# Demux.net
KiCad netlist of a schematic drawn in Altium Designer
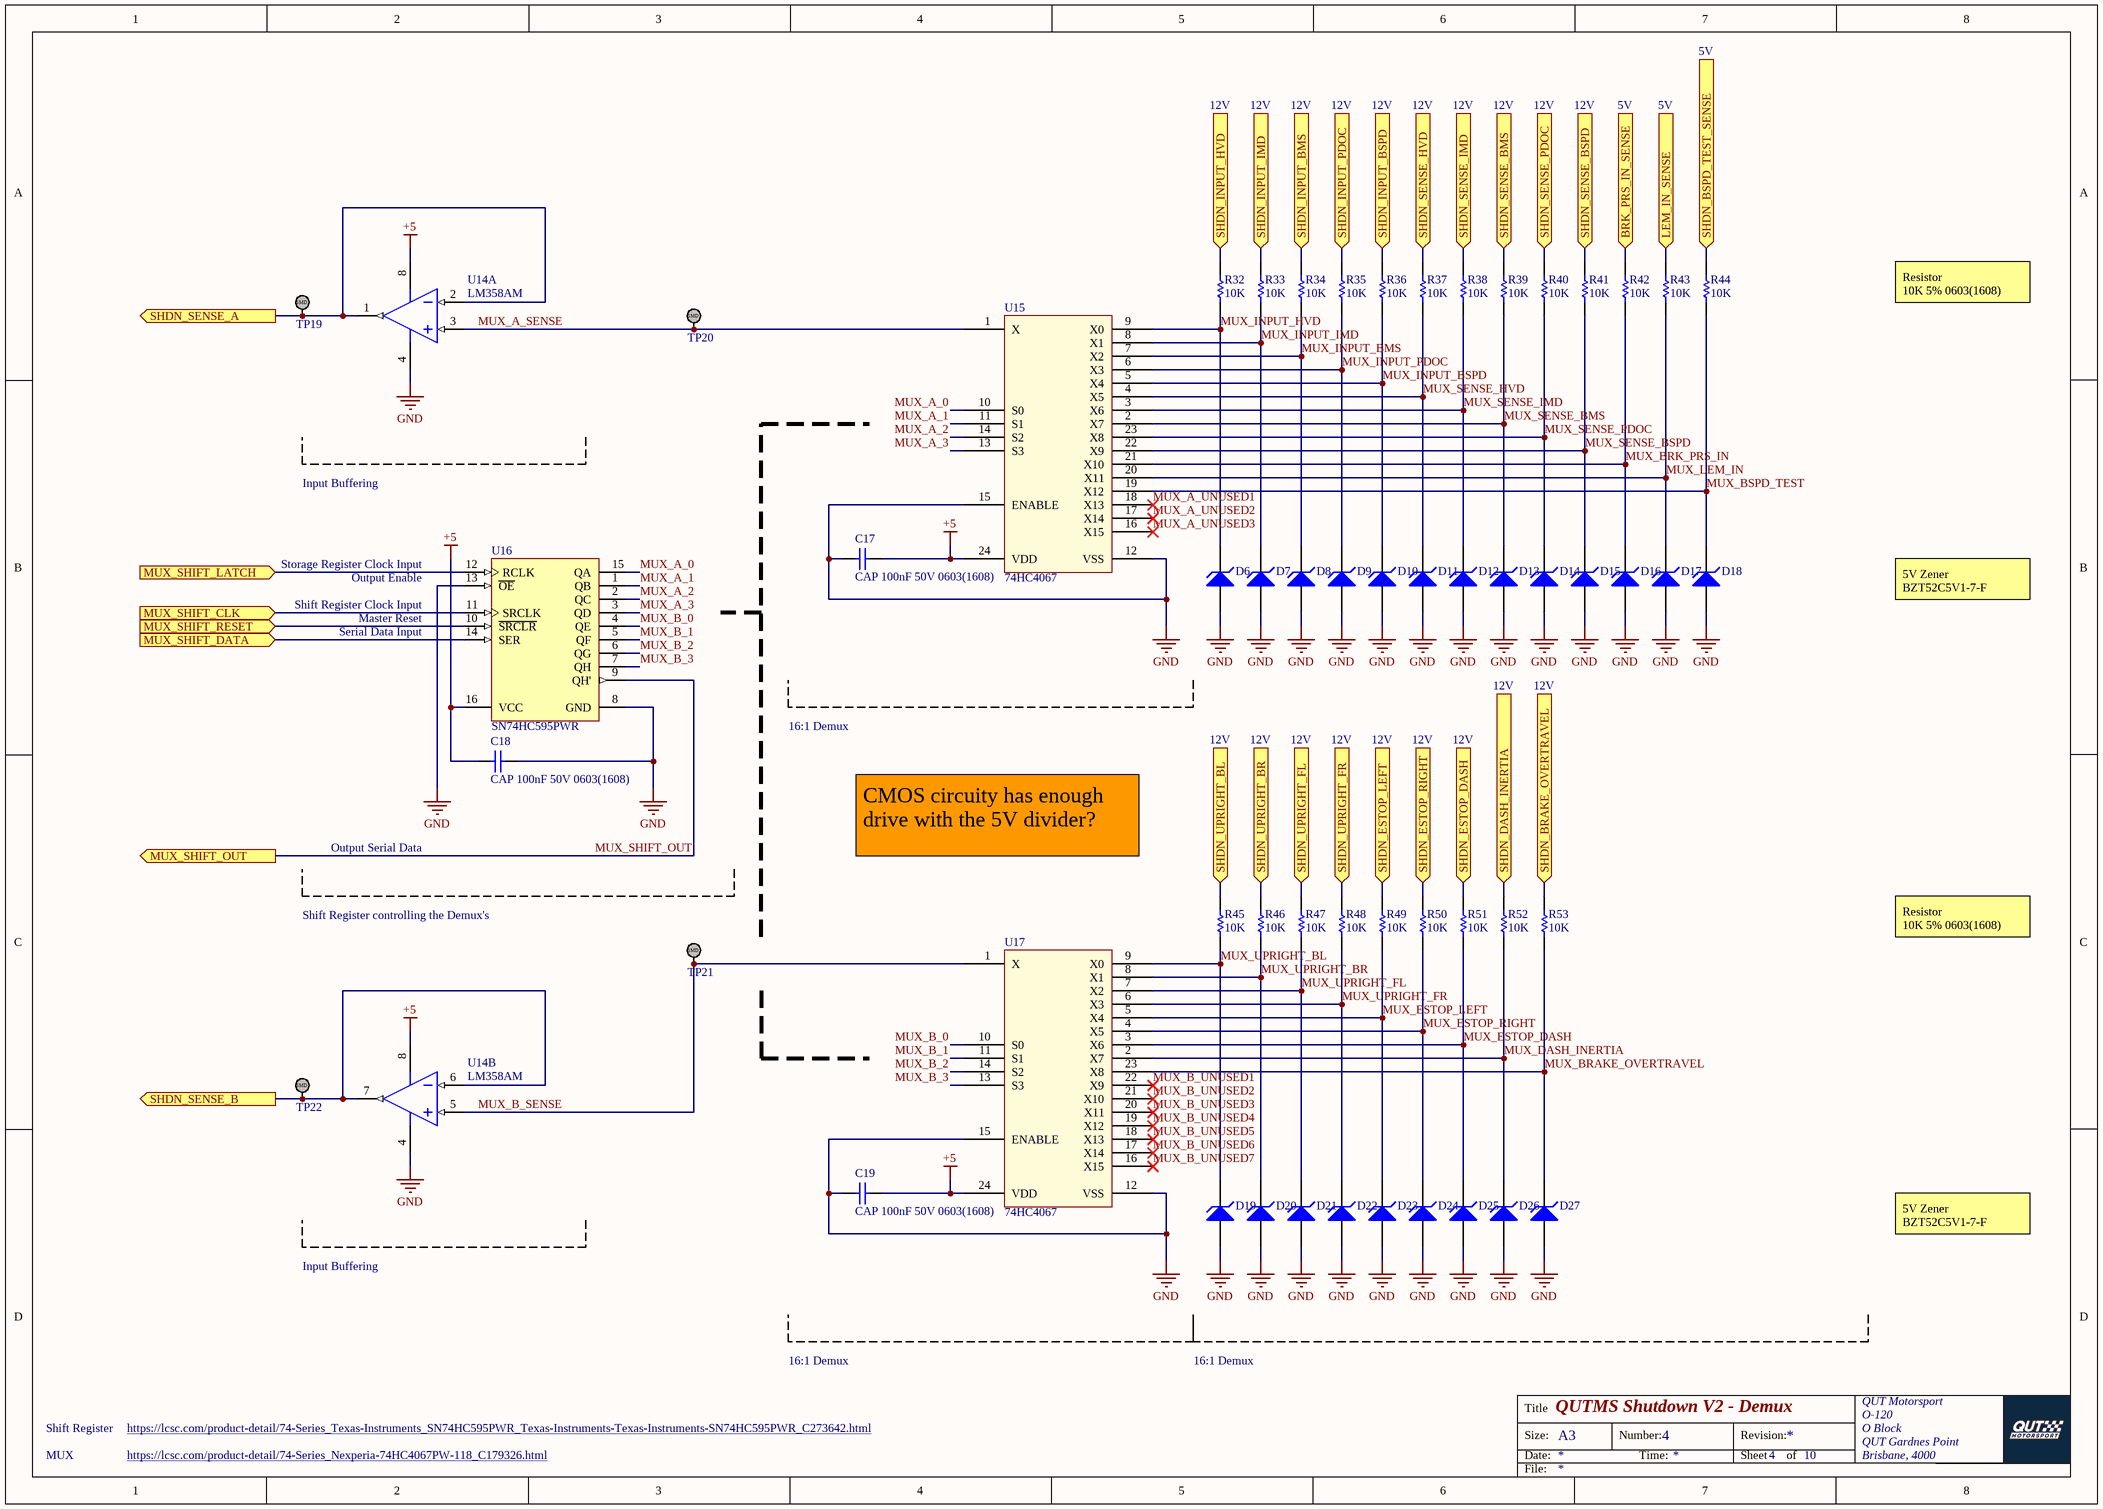
[diagram p0: Demux.SchDoc]

(export (version "E")
  (design (tool "Eeschema 10.0.6"))
  (components
    (comp (ref "C17")
      (value "CAP 100nF 50V 0603(1608)")
      (footprint "CAPC0603(1608)100_L")
      (description "CAP 100nF 50V ±5% 0603 (1608 Metric) Thickness 1mm SMD")
      (fields (field (name "TOLERANCE") "Â±5%"))
      (libsource (lib "Altium Content Vault") (part "CAP"))
    )
    (comp (ref "C18")
      (value "CAP 100nF 50V 0603(1608)")
      (footprint "CAPC0603(1608)100_L")
      (description "CAP 100nF 50V ±5% 0603 (1608 Metric) Thickness 1mm SMD")
      (fields (field (name "TOLERANCE") "Â±5%"))
      (libsource (lib "Altium Content Vault") (part "CAP"))
    )
    (comp (ref "C19")
      (value "CAP 100nF 50V 0603(1608)")
      (footprint "CAPC0603(1608)100_L")
      (description "CAP 100nF 50V ±5% 0603 (1608 Metric) Thickness 1mm SMD")
      (fields (field (name "TOLERANCE") "Â±5%"))
      (libsource (lib "Altium Content Vault") (part "CAP"))
    )
    (comp (ref "D6")
      (value "BZT52C5V1-7-F")
      (footprint "DIOD-SOD123_V")
      (description "Surface Mount Zener Diode, 5.1 V, -65 to 150 degC, 2-Pin SMD (SOD-123), RoHS, Tape and Reel")
      (fields (field (name "MANUFACTURER") "DiodesIncorporated"))
      (libsource (lib "Altium Content Vault") (part "DZEN-AK-2"))
    )
    (comp (ref "D7")
      (value "BZT52C5V1-7-F")
      (footprint "DIOD-SOD123_V")
      (description "Surface Mount Zener Diode, 5.1 V, -65 to 150 degC, 2-Pin SMD (SOD-123), RoHS, Tape and Reel")
      (fields (field (name "MANUFACTURER") "DiodesIncorporated"))
      (libsource (lib "Altium Content Vault") (part "DZEN-AK-2"))
    )
    (comp (ref "D8")
      (value "BZT52C5V1-7-F")
      (footprint "DIOD-SOD123_V")
      (description "Surface Mount Zener Diode, 5.1 V, -65 to 150 degC, 2-Pin SMD (SOD-123), RoHS, Tape and Reel")
      (fields (field (name "MANUFACTURER") "DiodesIncorporated"))
      (libsource (lib "Altium Content Vault") (part "DZEN-AK-2"))
    )
    (comp (ref "D9")
      (value "BZT52C5V1-7-F")
      (footprint "DIOD-SOD123_V")
      (description "Surface Mount Zener Diode, 5.1 V, -65 to 150 degC, 2-Pin SMD (SOD-123), RoHS, Tape and Reel")
      (fields (field (name "MANUFACTURER") "DiodesIncorporated"))
      (libsource (lib "Altium Content Vault") (part "DZEN-AK-2"))
    )
    (comp (ref "D10")
      (value "BZT52C5V1-7-F")
      (footprint "DIOD-SOD123_V")
      (description "Surface Mount Zener Diode, 5.1 V, -65 to 150 degC, 2-Pin SMD (SOD-123), RoHS, Tape and Reel")
      (fields (field (name "MANUFACTURER") "DiodesIncorporated"))
      (libsource (lib "Altium Content Vault") (part "DZEN-AK-2"))
    )
    (comp (ref "D11")
      (value "BZT52C5V1-7-F")
      (footprint "DIOD-SOD123_V")
      (description "Surface Mount Zener Diode, 5.1 V, -65 to 150 degC, 2-Pin SMD (SOD-123), RoHS, Tape and Reel")
      (fields (field (name "MANUFACTURER") "DiodesIncorporated"))
      (libsource (lib "Altium Content Vault") (part "DZEN-AK-2"))
    )
    (comp (ref "D12")
      (value "BZT52C5V1-7-F")
      (footprint "DIOD-SOD123_V")
      (description "Surface Mount Zener Diode, 5.1 V, -65 to 150 degC, 2-Pin SMD (SOD-123), RoHS, Tape and Reel")
      (fields (field (name "MANUFACTURER") "DiodesIncorporated"))
      (libsource (lib "Altium Content Vault") (part "DZEN-AK-2"))
    )
    (comp (ref "D13")
      (value "BZT52C5V1-7-F")
      (footprint "DIOD-SOD123_V")
      (description "Surface Mount Zener Diode, 5.1 V, -65 to 150 degC, 2-Pin SMD (SOD-123), RoHS, Tape and Reel")
      (fields (field (name "MANUFACTURER") "DiodesIncorporated"))
      (libsource (lib "Altium Content Vault") (part "DZEN-AK-2"))
    )
    (comp (ref "D14")
      (value "BZT52C5V1-7-F")
      (footprint "DIOD-SOD123_V")
      (description "Surface Mount Zener Diode, 5.1 V, -65 to 150 degC, 2-Pin SMD (SOD-123), RoHS, Tape and Reel")
      (fields (field (name "MANUFACTURER") "DiodesIncorporated"))
      (libsource (lib "Altium Content Vault") (part "DZEN-AK-2"))
    )
    (comp (ref "D15")
      (value "BZT52C5V1-7-F")
      (footprint "DIOD-SOD123_V")
      (description "Surface Mount Zener Diode, 5.1 V, -65 to 150 degC, 2-Pin SMD (SOD-123), RoHS, Tape and Reel")
      (fields (field (name "MANUFACTURER") "DiodesIncorporated"))
      (libsource (lib "Altium Content Vault") (part "DZEN-AK-2"))
    )
    (comp (ref "D16")
      (value "BZT52C5V1-7-F")
      (footprint "DIOD-SOD123_V")
      (description "Surface Mount Zener Diode, 5.1 V, -65 to 150 degC, 2-Pin SMD (SOD-123), RoHS, Tape and Reel")
      (fields (field (name "MANUFACTURER") "DiodesIncorporated"))
      (libsource (lib "Altium Content Vault") (part "DZEN-AK-2"))
    )
    (comp (ref "D17")
      (value "BZT52C5V1-7-F")
      (footprint "DIOD-SOD123_V")
      (description "Surface Mount Zener Diode, 5.1 V, -65 to 150 degC, 2-Pin SMD (SOD-123), RoHS, Tape and Reel")
      (fields (field (name "MANUFACTURER") "DiodesIncorporated"))
      (libsource (lib "Altium Content Vault") (part "DZEN-AK-2"))
    )
    (comp (ref "D18")
      (value "BZT52C5V1-7-F")
      (footprint "DIOD-SOD123_V")
      (description "Surface Mount Zener Diode, 5.1 V, -65 to 150 degC, 2-Pin SMD (SOD-123), RoHS, Tape and Reel")
      (fields (field (name "MANUFACTURER") "DiodesIncorporated"))
      (libsource (lib "Altium Content Vault") (part "DZEN-AK-2"))
    )
    (comp (ref "D19")
      (value "BZT52C5V1-7-F")
      (footprint "DIOD-SOD123_V")
      (description "Surface Mount Zener Diode, 5.1 V, -65 to 150 degC, 2-Pin SMD (SOD-123), RoHS, Tape and Reel")
      (fields (field (name "MANUFACTURER") "DiodesIncorporated"))
      (libsource (lib "Altium Content Vault") (part "DZEN-AK-2"))
    )
    (comp (ref "D20")
      (value "BZT52C5V1-7-F")
      (footprint "DIOD-SOD123_V")
      (description "Surface Mount Zener Diode, 5.1 V, -65 to 150 degC, 2-Pin SMD (SOD-123), RoHS, Tape and Reel")
      (fields (field (name "MANUFACTURER") "DiodesIncorporated"))
      (libsource (lib "Altium Content Vault") (part "DZEN-AK-2"))
    )
    (comp (ref "D21")
      (value "BZT52C5V1-7-F")
      (footprint "DIOD-SOD123_V")
      (description "Surface Mount Zener Diode, 5.1 V, -65 to 150 degC, 2-Pin SMD (SOD-123), RoHS, Tape and Reel")
      (fields (field (name "MANUFACTURER") "DiodesIncorporated"))
      (libsource (lib "Altium Content Vault") (part "DZEN-AK-2"))
    )
    (comp (ref "D22")
      (value "BZT52C5V1-7-F")
      (footprint "DIOD-SOD123_V")
      (description "Surface Mount Zener Diode, 5.1 V, -65 to 150 degC, 2-Pin SMD (SOD-123), RoHS, Tape and Reel")
      (fields (field (name "MANUFACTURER") "DiodesIncorporated"))
      (libsource (lib "Altium Content Vault") (part "DZEN-AK-2"))
    )
    (comp (ref "D23")
      (value "BZT52C5V1-7-F")
      (footprint "DIOD-SOD123_V")
      (description "Surface Mount Zener Diode, 5.1 V, -65 to 150 degC, 2-Pin SMD (SOD-123), RoHS, Tape and Reel")
      (fields (field (name "MANUFACTURER") "DiodesIncorporated"))
      (libsource (lib "Altium Content Vault") (part "DZEN-AK-2"))
    )
    (comp (ref "D24")
      (value "BZT52C5V1-7-F")
      (footprint "DIOD-SOD123_V")
      (description "Surface Mount Zener Diode, 5.1 V, -65 to 150 degC, 2-Pin SMD (SOD-123), RoHS, Tape and Reel")
      (fields (field (name "MANUFACTURER") "DiodesIncorporated"))
      (libsource (lib "Altium Content Vault") (part "DZEN-AK-2"))
    )
    (comp (ref "D25")
      (value "BZT52C5V1-7-F")
      (footprint "DIOD-SOD123_V")
      (description "Surface Mount Zener Diode, 5.1 V, -65 to 150 degC, 2-Pin SMD (SOD-123), RoHS, Tape and Reel")
      (fields (field (name "MANUFACTURER") "DiodesIncorporated"))
      (libsource (lib "Altium Content Vault") (part "DZEN-AK-2"))
    )
    (comp (ref "D26")
      (value "BZT52C5V1-7-F")
      (footprint "DIOD-SOD123_V")
      (description "Surface Mount Zener Diode, 5.1 V, -65 to 150 degC, 2-Pin SMD (SOD-123), RoHS, Tape and Reel")
      (fields (field (name "MANUFACTURER") "DiodesIncorporated"))
      (libsource (lib "Altium Content Vault") (part "DZEN-AK-2"))
    )
    (comp (ref "D27")
      (value "BZT52C5V1-7-F")
      (footprint "DIOD-SOD123_V")
      (description "Surface Mount Zener Diode, 5.1 V, -65 to 150 degC, 2-Pin SMD (SOD-123), RoHS, Tape and Reel")
      (fields (field (name "MANUFACTURER") "DiodesIncorporated"))
      (libsource (lib "Altium Content Vault") (part "DZEN-AK-2"))
    )
    (comp (ref "R32")
      (value "10K")
      (footprint "RESC0603(1608)_N")
      (description "10K 0.1W 5% 0603 (1608 Metric)  SMD")
      (fields (field (name "TOLERANCE") "5 %") (field (name "POWER") "0.1 W"))
      (libsource (lib "Altium Content Vault") (part "RES"))
    )
    (comp (ref "R33")
      (value "10K")
      (footprint "RESC0603(1608)_N")
      (description "10K 0.1W 5% 0603 (1608 Metric)  SMD")
      (fields (field (name "TOLERANCE") "5 %") (field (name "POWER") "0.1 W"))
      (libsource (lib "Altium Content Vault") (part "RES"))
    )
    (comp (ref "R34")
      (value "10K")
      (footprint "RESC0603(1608)_N")
      (description "10K 0.1W 5% 0603 (1608 Metric)  SMD")
      (fields (field (name "TOLERANCE") "5 %") (field (name "POWER") "0.1 W"))
      (libsource (lib "Altium Content Vault") (part "RES"))
    )
    (comp (ref "R35")
      (value "10K")
      (footprint "RESC0603(1608)_N")
      (description "10K 0.1W 5% 0603 (1608 Metric)  SMD")
      (fields (field (name "TOLERANCE") "5 %") (field (name "POWER") "0.1 W"))
      (libsource (lib "Altium Content Vault") (part "RES"))
    )
    (comp (ref "R36")
      (value "10K")
      (footprint "RESC0603(1608)_N")
      (description "10K 0.1W 5% 0603 (1608 Metric)  SMD")
      (fields (field (name "TOLERANCE") "5 %") (field (name "POWER") "0.1 W"))
      (libsource (lib "Altium Content Vault") (part "RES"))
    )
    (comp (ref "R37")
      (value "10K")
      (footprint "RESC0603(1608)_N")
      (description "10K 0.1W 5% 0603 (1608 Metric)  SMD")
      (fields (field (name "TOLERANCE") "5 %") (field (name "POWER") "0.1 W"))
      (libsource (lib "Altium Content Vault") (part "RES"))
    )
    (comp (ref "R38")
      (value "10K")
      (footprint "RESC0603(1608)_N")
      (description "10K 0.1W 5% 0603 (1608 Metric)  SMD")
      (fields (field (name "TOLERANCE") "5 %") (field (name "POWER") "0.1 W"))
      (libsource (lib "Altium Content Vault") (part "RES"))
    )
    (comp (ref "R39")
      (value "10K")
      (footprint "RESC0603(1608)_N")
      (description "10K 0.1W 5% 0603 (1608 Metric)  SMD")
      (fields (field (name "TOLERANCE") "5 %") (field (name "POWER") "0.1 W"))
      (libsource (lib "Altium Content Vault") (part "RES"))
    )
    (comp (ref "R40")
      (value "10K")
      (footprint "RESC0603(1608)_N")
      (description "10K 0.1W 5% 0603 (1608 Metric)  SMD")
      (fields (field (name "TOLERANCE") "5 %") (field (name "POWER") "0.1 W"))
      (libsource (lib "Altium Content Vault") (part "RES"))
    )
    (comp (ref "R41")
      (value "10K")
      (footprint "RESC0603(1608)_N")
      (description "10K 0.1W 5% 0603 (1608 Metric)  SMD")
      (fields (field (name "TOLERANCE") "5 %") (field (name "POWER") "0.1 W"))
      (libsource (lib "Altium Content Vault") (part "RES"))
    )
    (comp (ref "R42")
      (value "10K")
      (footprint "RESC0603(1608)_N")
      (description "10K 0.1W 5% 0603 (1608 Metric)  SMD")
      (fields (field (name "TOLERANCE") "5 %") (field (name "POWER") "0.1 W"))
      (libsource (lib "Altium Content Vault") (part "RES"))
    )
    (comp (ref "R43")
      (value "10K")
      (footprint "RESC0603(1608)_N")
      (description "10K 0.1W 5% 0603 (1608 Metric)  SMD")
      (fields (field (name "TOLERANCE") "5 %") (field (name "POWER") "0.1 W"))
      (libsource (lib "Altium Content Vault") (part "RES"))
    )
    (comp (ref "R44")
      (value "10K")
      (footprint "RESC0603(1608)_N")
      (description "10K 0.1W 5% 0603 (1608 Metric)  SMD")
      (fields (field (name "TOLERANCE") "5 %") (field (name "POWER") "0.1 W"))
      (libsource (lib "Altium Content Vault") (part "RES"))
    )
    (comp (ref "R45")
      (value "10K")
      (footprint "RESC0603(1608)_N")
      (description "10K 0.1W 5% 0603 (1608 Metric)  SMD")
      (fields (field (name "TOLERANCE") "5 %") (field (name "POWER") "0.1 W"))
      (libsource (lib "Altium Content Vault") (part "RES"))
    )
    (comp (ref "R46")
      (value "10K")
      (footprint "RESC0603(1608)_N")
      (description "10K 0.1W 5% 0603 (1608 Metric)  SMD")
      (fields (field (name "TOLERANCE") "5 %") (field (name "POWER") "0.1 W"))
      (libsource (lib "Altium Content Vault") (part "RES"))
    )
    (comp (ref "R47")
      (value "10K")
      (footprint "RESC0603(1608)_N")
      (description "10K 0.1W 5% 0603 (1608 Metric)  SMD")
      (fields (field (name "TOLERANCE") "5 %") (field (name "POWER") "0.1 W"))
      (libsource (lib "Altium Content Vault") (part "RES"))
    )
    (comp (ref "R48")
      (value "10K")
      (footprint "RESC0603(1608)_N")
      (description "10K 0.1W 5% 0603 (1608 Metric)  SMD")
      (fields (field (name "TOLERANCE") "5 %") (field (name "POWER") "0.1 W"))
      (libsource (lib "Altium Content Vault") (part "RES"))
    )
    (comp (ref "R49")
      (value "10K")
      (footprint "RESC0603(1608)_N")
      (description "10K 0.1W 5% 0603 (1608 Metric)  SMD")
      (fields (field (name "TOLERANCE") "5 %") (field (name "POWER") "0.1 W"))
      (libsource (lib "Altium Content Vault") (part "RES"))
    )
    (comp (ref "R50")
      (value "10K")
      (footprint "RESC0603(1608)_N")
      (description "10K 0.1W 5% 0603 (1608 Metric)  SMD")
      (fields (field (name "TOLERANCE") "5 %") (field (name "POWER") "0.1 W"))
      (libsource (lib "Altium Content Vault") (part "RES"))
    )
    (comp (ref "R51")
      (value "10K")
      (footprint "RESC0603(1608)_N")
      (description "10K 0.1W 5% 0603 (1608 Metric)  SMD")
      (fields (field (name "TOLERANCE") "5 %") (field (name "POWER") "0.1 W"))
      (libsource (lib "Altium Content Vault") (part "RES"))
    )
    (comp (ref "R52")
      (value "10K")
      (footprint "RESC0603(1608)_N")
      (description "10K 0.1W 5% 0603 (1608 Metric)  SMD")
      (fields (field (name "TOLERANCE") "5 %") (field (name "POWER") "0.1 W"))
      (libsource (lib "Altium Content Vault") (part "RES"))
    )
    (comp (ref "R53")
      (value "10K")
      (footprint "RESC0603(1608)_N")
      (description "10K 0.1W 5% 0603 (1608 Metric)  SMD")
      (fields (field (name "TOLERANCE") "5 %") (field (name "POWER") "0.1 W"))
      (libsource (lib "Altium Content Vault") (part "RES"))
    )
    (comp (ref "TP19")
      (value "TestPoint_SMD")
      (footprint "TestPointSMD")
      (libsource (lib "StandardTest") (part "TestPoint_SMD"))
    )
    (comp (ref "TP20")
      (value "TestPoint_SMD")
      (footprint "TestPointSMD")
      (libsource (lib "StandardTest") (part "TestPoint_SMD"))
    )
    (comp (ref "TP21")
      (value "TestPoint_SMD")
      (footprint "TestPointSMD")
      (libsource (lib "StandardTest") (part "TestPoint_SMD"))
    )
    (comp (ref "TP22")
      (value "TestPoint_SMD")
      (footprint "TestPointSMD")
      (libsource (lib "StandardTest") (part "TestPoint_SMD"))
    )
    (comp (ref "U14")
      (value "LM358AM")
      (footprint "D0008A_M")
      (description "Low Power Dual Operational Amplifier, 8-pin Narrow SOIC")
      (fields (field (name "MANUFACTURER") "Texas Instruments"))
      (libsource (lib "Altium Content Vault") (part "AMP-OPA-LM158-8"))
    )
    (comp (ref "U15")
      (value "74HC4067")
      (footprint "74HC4067 TSSOP24")
      (libsource (lib "QUTMS_MUXLibrary") (part "74HC4067"))
    )
    (comp (ref "U16")
      (value "SN74HC595PWR")
      (footprint "PW0016A_L")
      (description "8-Bit Shift Registers With 3-State Output Registers, PW0016A, LARGE T&R")
      (fields
        (field (name "GENERIC PART NUMBER") "SN74HC595")
        (field (name "MANUFACTURER") "Texas Instruments")
      )
      (libsource (lib "Altium Content Vault") (part "TI-SN74XHCT595X_SN74LV595A-16"))
    )
    (comp (ref "U17")
      (value "74HC4067")
      (footprint "74HC4067 TSSOP24")
      (libsource (lib "QUTMS_MUXLibrary") (part "74HC4067"))
    )
  )
  (nets
    (net (code "1") (name "+5") (class "Default")
      (node (ref "C17") (pin "1") (pinfunction "1_1") (pintype "passive"))
      (node (ref "C18") (pin "2") (pinfunction "2_2") (pintype "passive"))
      (node (ref "C19") (pin "1") (pinfunction "1_1") (pintype "passive"))
      (node (ref "U14") (pin "8") (pinfunction "V+_8") (pintype "power_in"))
      (node (ref "U15") (pin "24") (pinfunction "VDD_24") (pintype "passive"))
      (node (ref "U16") (pin "16") (pinfunction "VCC_16") (pintype "power_in"))
      (node (ref "U17") (pin "24") (pinfunction "VDD_24") (pintype "passive"))
    )
    (net (code "2") (name "/BRK_PRS_IN_SENSE") (class "Default")
      (node (ref "R42") (pin "1") (pinfunction "1_1") (pintype "passive"))
    )
    (net (code "3") (name "/LEM_IN_SENSE") (class "Default")
      (node (ref "R43") (pin "1") (pinfunction "1_1") (pintype "passive"))
    )
    (net (code "4") (name "/MUX_A_0") (class "Default")
      (node (ref "U15") (pin "10") (pinfunction "S0_10") (pintype "passive"))
      (node (ref "U16") (pin "15") (pinfunction "QA_15") (pintype "tri_state"))
    )
    (net (code "5") (name "/MUX_A_1") (class "Default")
      (node (ref "U15") (pin "11") (pinfunction "S1_11") (pintype "passive"))
      (node (ref "U16") (pin "1") (pinfunction "QB_1") (pintype "tri_state"))
    )
    (net (code "6") (name "/MUX_A_2") (class "Default")
      (node (ref "U15") (pin "14") (pinfunction "S2_14") (pintype "passive"))
      (node (ref "U16") (pin "2") (pinfunction "QC_2") (pintype "tri_state"))
    )
    (net (code "7") (name "/MUX_A_3") (class "Default")
      (node (ref "U15") (pin "13") (pinfunction "S3_13") (pintype "passive"))
      (node (ref "U16") (pin "3") (pinfunction "QD_3") (pintype "tri_state"))
    )
    (net (code "8") (name "/MUX_A_SENSE") (class "Default")
      (node (ref "TP20") (pin "1") (pinfunction "1_1") (pintype "passive"))
      (node (ref "U14") (pin "3") (pinfunction "INA+_3") (pintype "input"))
      (node (ref "U15") (pin "1") (pinfunction "X_1") (pintype "passive"))
    )
    (net (code "9") (name "/MUX_A_UNUSED1") (class "Default")
      (node (ref "U15") (pin "18") (pinfunction "X13_18") (pintype "passive+no_connect"))
    )
    (net (code "10") (name "/MUX_A_UNUSED2") (class "Default")
      (node (ref "U15") (pin "17") (pinfunction "X14_17") (pintype "passive+no_connect"))
    )
    (net (code "11") (name "/MUX_A_UNUSED3") (class "Default")
      (node (ref "U15") (pin "16") (pinfunction "X15_16") (pintype "passive+no_connect"))
    )
    (net (code "12") (name "/MUX_BRAKE_OVERTRAVEL") (class "Default")
      (node (ref "D27") (pin "2") (pinfunction "K_2") (pintype "passive"))
      (node (ref "R53") (pin "2") (pinfunction "2_2") (pintype "passive"))
      (node (ref "U17") (pin "23") (pinfunction "X8_23") (pintype "passive"))
    )
    (net (code "13") (name "/MUX_BRK_PRS_IN") (class "Default")
      (node (ref "D16") (pin "2") (pinfunction "K_2") (pintype "passive"))
      (node (ref "R42") (pin "2") (pinfunction "2_2") (pintype "passive"))
      (node (ref "U15") (pin "21") (pinfunction "X10_21") (pintype "passive"))
    )
    (net (code "14") (name "/MUX_BSPD_TEST") (class "Default")
      (node (ref "D18") (pin "2") (pinfunction "K_2") (pintype "passive"))
      (node (ref "R44") (pin "2") (pinfunction "2_2") (pintype "passive"))
      (node (ref "U15") (pin "19") (pinfunction "X12_19") (pintype "passive"))
    )
    (net (code "15") (name "/MUX_B_0") (class "Default")
      (node (ref "U16") (pin "4") (pinfunction "QE_4") (pintype "tri_state"))
      (node (ref "U17") (pin "10") (pinfunction "S0_10") (pintype "passive"))
    )
    (net (code "16") (name "/MUX_B_1") (class "Default")
      (node (ref "U16") (pin "5") (pinfunction "QF_5") (pintype "tri_state"))
      (node (ref "U17") (pin "11") (pinfunction "S1_11") (pintype "passive"))
    )
    (net (code "17") (name "/MUX_B_2") (class "Default")
      (node (ref "U16") (pin "6") (pinfunction "QG_6") (pintype "tri_state"))
      (node (ref "U17") (pin "14") (pinfunction "S2_14") (pintype "passive"))
    )
    (net (code "18") (name "/MUX_B_3") (class "Default")
      (node (ref "U16") (pin "7") (pinfunction "QH_7") (pintype "tri_state"))
      (node (ref "U17") (pin "13") (pinfunction "S3_13") (pintype "passive"))
    )
    (net (code "19") (name "/MUX_B_SENSE") (class "Default")
      (node (ref "TP21") (pin "1") (pinfunction "1_1") (pintype "passive"))
      (node (ref "U14") (pin "5") (pinfunction "INB+_5") (pintype "input"))
      (node (ref "U17") (pin "1") (pinfunction "X_1") (pintype "passive"))
    )
    (net (code "20") (name "/MUX_B_UNUSED1") (class "Default")
      (node (ref "U17") (pin "22") (pinfunction "X9_22") (pintype "passive+no_connect"))
    )
    (net (code "21") (name "/MUX_B_UNUSED2") (class "Default")
      (node (ref "U17") (pin "21") (pinfunction "X10_21") (pintype "passive+no_connect"))
    )
    (net (code "22") (name "/MUX_B_UNUSED3") (class "Default")
      (node (ref "U17") (pin "20") (pinfunction "X11_20") (pintype "passive+no_connect"))
    )
    (net (code "23") (name "/MUX_B_UNUSED4") (class "Default")
      (node (ref "U17") (pin "19") (pinfunction "X12_19") (pintype "passive+no_connect"))
    )
    (net (code "24") (name "/MUX_B_UNUSED5") (class "Default")
      (node (ref "U17") (pin "18") (pinfunction "X13_18") (pintype "passive+no_connect"))
    )
    (net (code "25") (name "/MUX_B_UNUSED6") (class "Default")
      (node (ref "U17") (pin "17") (pinfunction "X14_17") (pintype "passive+no_connect"))
    )
    (net (code "26") (name "/MUX_B_UNUSED7") (class "Default")
      (node (ref "U17") (pin "16") (pinfunction "X15_16") (pintype "passive+no_connect"))
    )
    (net (code "27") (name "/MUX_DASH_INERTIA") (class "Default")
      (node (ref "D26") (pin "2") (pinfunction "K_2") (pintype "passive"))
      (node (ref "R52") (pin "2") (pinfunction "2_2") (pintype "passive"))
      (node (ref "U17") (pin "2") (pinfunction "X7_2") (pintype "passive"))
    )
    (net (code "28") (name "/MUX_ESTOP_DASH") (class "Default")
      (node (ref "D25") (pin "2") (pinfunction "K_2") (pintype "passive"))
      (node (ref "R51") (pin "2") (pinfunction "2_2") (pintype "passive"))
      (node (ref "U17") (pin "3") (pinfunction "X6_3") (pintype "passive"))
    )
    (net (code "29") (name "/MUX_ESTOP_LEFT") (class "Default")
      (node (ref "D23") (pin "2") (pinfunction "K_2") (pintype "passive"))
      (node (ref "R49") (pin "2") (pinfunction "2_2") (pintype "passive"))
      (node (ref "U17") (pin "5") (pinfunction "X4_5") (pintype "passive"))
    )
    (net (code "30") (name "/MUX_ESTOP_RIGHT") (class "Default")
      (node (ref "D24") (pin "2") (pinfunction "K_2") (pintype "passive"))
      (node (ref "R50") (pin "2") (pinfunction "2_2") (pintype "passive"))
      (node (ref "U17") (pin "4") (pinfunction "X5_4") (pintype "passive"))
    )
    (net (code "31") (name "/MUX_INPUT_BMS") (class "Default")
      (node (ref "D8") (pin "2") (pinfunction "K_2") (pintype "passive"))
      (node (ref "R34") (pin "2") (pinfunction "2_2") (pintype "passive"))
      (node (ref "U15") (pin "7") (pinfunction "X2_7") (pintype "passive"))
    )
    (net (code "32") (name "/MUX_INPUT_BSPD") (class "Default")
      (node (ref "D10") (pin "2") (pinfunction "K_2") (pintype "passive"))
      (node (ref "R36") (pin "2") (pinfunction "2_2") (pintype "passive"))
      (node (ref "U15") (pin "5") (pinfunction "X4_5") (pintype "passive"))
    )
    (net (code "33") (name "/MUX_INPUT_HVD") (class "Default")
      (node (ref "D6") (pin "2") (pinfunction "K_2") (pintype "passive"))
      (node (ref "R32") (pin "2") (pinfunction "2_2") (pintype "passive"))
      (node (ref "U15") (pin "9") (pinfunction "X0_9") (pintype "passive"))
    )
    (net (code "34") (name "/MUX_INPUT_IMD") (class "Default")
      (node (ref "D7") (pin "2") (pinfunction "K_2") (pintype "passive"))
      (node (ref "R33") (pin "2") (pinfunction "2_2") (pintype "passive"))
      (node (ref "U15") (pin "8") (pinfunction "X1_8") (pintype "passive"))
    )
    (net (code "35") (name "/MUX_INPUT_PDOC") (class "Default")
      (node (ref "D9") (pin "2") (pinfunction "K_2") (pintype "passive"))
      (node (ref "R35") (pin "2") (pinfunction "2_2") (pintype "passive"))
      (node (ref "U15") (pin "6") (pinfunction "X3_6") (pintype "passive"))
    )
    (net (code "36") (name "/MUX_LEM_IN") (class "Default")
      (node (ref "D17") (pin "2") (pinfunction "K_2") (pintype "passive"))
      (node (ref "R43") (pin "2") (pinfunction "2_2") (pintype "passive"))
      (node (ref "U15") (pin "20") (pinfunction "X11_20") (pintype "passive"))
    )
    (net (code "37") (name "/MUX_SENSE_BMS") (class "Default")
      (node (ref "D13") (pin "2") (pinfunction "K_2") (pintype "passive"))
      (node (ref "R39") (pin "2") (pinfunction "2_2") (pintype "passive"))
      (node (ref "U15") (pin "2") (pinfunction "X7_2") (pintype "passive"))
    )
    (net (code "38") (name "/MUX_SENSE_BSPD") (class "Default")
      (node (ref "D15") (pin "2") (pinfunction "K_2") (pintype "passive"))
      (node (ref "R41") (pin "2") (pinfunction "2_2") (pintype "passive"))
      (node (ref "U15") (pin "22") (pinfunction "X9_22") (pintype "passive"))
    )
    (net (code "39") (name "/MUX_SENSE_HVD") (class "Default")
      (node (ref "D11") (pin "2") (pinfunction "K_2") (pintype "passive"))
      (node (ref "R37") (pin "2") (pinfunction "2_2") (pintype "passive"))
      (node (ref "U15") (pin "4") (pinfunction "X5_4") (pintype "passive"))
    )
    (net (code "40") (name "/MUX_SENSE_IMD") (class "Default")
      (node (ref "D12") (pin "2") (pinfunction "K_2") (pintype "passive"))
      (node (ref "R38") (pin "2") (pinfunction "2_2") (pintype "passive"))
      (node (ref "U15") (pin "3") (pinfunction "X6_3") (pintype "passive"))
    )
    (net (code "41") (name "/MUX_SENSE_PDOC") (class "Default")
      (node (ref "D14") (pin "2") (pinfunction "K_2") (pintype "passive"))
      (node (ref "R40") (pin "2") (pinfunction "2_2") (pintype "passive"))
      (node (ref "U15") (pin "23") (pinfunction "X8_23") (pintype "passive"))
    )
    (net (code "42") (name "/MUX_SHIFT_CLK") (class "Default")
      (node (ref "U16") (pin "11") (pinfunction "SRCLK_11") (pintype "input"))
    )
    (net (code "43") (name "/MUX_SHIFT_DATA") (class "Default")
      (node (ref "U16") (pin "14") (pinfunction "SER_14") (pintype "input"))
    )
    (net (code "44") (name "/MUX_SHIFT_LATCH") (class "Default")
      (node (ref "U16") (pin "12") (pinfunction "RCLK_12") (pintype "input"))
    )
    (net (code "45") (name "/MUX_SHIFT_OUT") (class "Default")
      (node (ref "U16") (pin "9") (pinfunction "QH'_9") (pintype "output"))
    )
    (net (code "46") (name "/MUX_SHIFT_RESET") (class "Default")
      (node (ref "U16") (pin "10") (pinfunction "~{SRCLR}_10") (pintype "input"))
    )
    (net (code "47") (name "/MUX_UPRIGHT_BL") (class "Default")
      (node (ref "D19") (pin "2") (pinfunction "K_2") (pintype "passive"))
      (node (ref "R45") (pin "2") (pinfunction "2_2") (pintype "passive"))
      (node (ref "U17") (pin "9") (pinfunction "X0_9") (pintype "passive"))
    )
    (net (code "48") (name "/MUX_UPRIGHT_BR") (class "Default")
      (node (ref "D20") (pin "2") (pinfunction "K_2") (pintype "passive"))
      (node (ref "R46") (pin "2") (pinfunction "2_2") (pintype "passive"))
      (node (ref "U17") (pin "8") (pinfunction "X1_8") (pintype "passive"))
    )
    (net (code "49") (name "/MUX_UPRIGHT_FL") (class "Default")
      (node (ref "D21") (pin "2") (pinfunction "K_2") (pintype "passive"))
      (node (ref "R47") (pin "2") (pinfunction "2_2") (pintype "passive"))
      (node (ref "U17") (pin "7") (pinfunction "X2_7") (pintype "passive"))
    )
    (net (code "50") (name "/MUX_UPRIGHT_FR") (class "Default")
      (node (ref "D22") (pin "2") (pinfunction "K_2") (pintype "passive"))
      (node (ref "R48") (pin "2") (pinfunction "2_2") (pintype "passive"))
      (node (ref "U17") (pin "6") (pinfunction "X3_6") (pintype "passive"))
    )
    (net (code "51") (name "/SHDN_BRAKE_OVERTRAVEL") (class "Default")
      (node (ref "R53") (pin "1") (pinfunction "1_1") (pintype "passive"))
    )
    (net (code "52") (name "/SHDN_BSPD_TEST_SENSE") (class "Default")
      (node (ref "R44") (pin "1") (pinfunction "1_1") (pintype "passive"))
    )
    (net (code "53") (name "/SHDN_DASH_INERTIA") (class "Default")
      (node (ref "R52") (pin "1") (pinfunction "1_1") (pintype "passive"))
    )
    (net (code "54") (name "/SHDN_ESTOP_DASH") (class "Default")
      (node (ref "R51") (pin "1") (pinfunction "1_1") (pintype "passive"))
    )
    (net (code "55") (name "/SHDN_ESTOP_LEFT") (class "Default")
      (node (ref "R49") (pin "1") (pinfunction "1_1") (pintype "passive"))
    )
    (net (code "56") (name "/SHDN_ESTOP_RIGHT") (class "Default")
      (node (ref "R50") (pin "1") (pinfunction "1_1") (pintype "passive"))
    )
    (net (code "57") (name "/SHDN_INPUT_BMS") (class "Default")
      (node (ref "R34") (pin "1") (pinfunction "1_1") (pintype "passive"))
    )
    (net (code "58") (name "/SHDN_INPUT_BSPD") (class "Default")
      (node (ref "R36") (pin "1") (pinfunction "1_1") (pintype "passive"))
    )
    (net (code "59") (name "/SHDN_INPUT_HVD") (class "Default")
      (node (ref "R32") (pin "1") (pinfunction "1_1") (pintype "passive"))
    )
    (net (code "60") (name "/SHDN_INPUT_IMD") (class "Default")
      (node (ref "R33") (pin "1") (pinfunction "1_1") (pintype "passive"))
    )
    (net (code "61") (name "/SHDN_INPUT_PDOC") (class "Default")
      (node (ref "R35") (pin "1") (pinfunction "1_1") (pintype "passive"))
    )
    (net (code "62") (name "/SHDN_SENSE_A") (class "Default")
      (node (ref "TP19") (pin "1") (pinfunction "1_1") (pintype "passive"))
      (node (ref "U14") (pin "1") (pinfunction "OUTA_1") (pintype "output"))
      (node (ref "U14") (pin "2") (pinfunction "INA-_2") (pintype "input"))
    )
    (net (code "63") (name "/SHDN_SENSE_B") (class "Default")
      (node (ref "TP22") (pin "1") (pinfunction "1_1") (pintype "passive"))
      (node (ref "U14") (pin "6") (pinfunction "INB-_6") (pintype "input"))
      (node (ref "U14") (pin "7") (pinfunction "OUTB_7") (pintype "output"))
    )
    (net (code "64") (name "/SHDN_SENSE_BMS") (class "Default")
      (node (ref "R39") (pin "1") (pinfunction "1_1") (pintype "passive"))
    )
    (net (code "65") (name "/SHDN_SENSE_BSPD") (class "Default")
      (node (ref "R41") (pin "1") (pinfunction "1_1") (pintype "passive"))
    )
    (net (code "66") (name "/SHDN_SENSE_HVD") (class "Default")
      (node (ref "R37") (pin "1") (pinfunction "1_1") (pintype "passive"))
    )
    (net (code "67") (name "/SHDN_SENSE_IMD") (class "Default")
      (node (ref "R38") (pin "1") (pinfunction "1_1") (pintype "passive"))
    )
    (net (code "68") (name "/SHDN_SENSE_PDOC") (class "Default")
      (node (ref "R40") (pin "1") (pinfunction "1_1") (pintype "passive"))
    )
    (net (code "69") (name "/SHDN_UPRIGHT_BL") (class "Default")
      (node (ref "R45") (pin "1") (pinfunction "1_1") (pintype "passive"))
    )
    (net (code "70") (name "/SHDN_UPRIGHT_BR") (class "Default")
      (node (ref "R46") (pin "1") (pinfunction "1_1") (pintype "passive"))
    )
    (net (code "71") (name "/SHDN_UPRIGHT_FL") (class "Default")
      (node (ref "R47") (pin "1") (pinfunction "1_1") (pintype "passive"))
    )
    (net (code "72") (name "/SHDN_UPRIGHT_FR") (class "Default")
      (node (ref "R48") (pin "1") (pinfunction "1_1") (pintype "passive"))
    )
    (net (code "73") (name "GND") (class "Default")
      (node (ref "C17") (pin "2") (pinfunction "2_2") (pintype "passive"))
      (node (ref "C18") (pin "1") (pinfunction "1_1") (pintype "passive"))
      (node (ref "C19") (pin "2") (pinfunction "2_2") (pintype "passive"))
      (node (ref "D10") (pin "1") (pinfunction "A_1") (pintype "passive"))
      (node (ref "D11") (pin "1") (pinfunction "A_1") (pintype "passive"))
      (node (ref "D12") (pin "1") (pinfunction "A_1") (pintype "passive"))
      (node (ref "D13") (pin "1") (pinfunction "A_1") (pintype "passive"))
      (node (ref "D14") (pin "1") (pinfunction "A_1") (pintype "passive"))
      (node (ref "D15") (pin "1") (pinfunction "A_1") (pintype "passive"))
      (node (ref "D16") (pin "1") (pinfunction "A_1") (pintype "passive"))
      (node (ref "D17") (pin "1") (pinfunction "A_1") (pintype "passive"))
      (node (ref "D18") (pin "1") (pinfunction "A_1") (pintype "passive"))
      (node (ref "D19") (pin "1") (pinfunction "A_1") (pintype "passive"))
      (node (ref "D20") (pin "1") (pinfunction "A_1") (pintype "passive"))
      (node (ref "D21") (pin "1") (pinfunction "A_1") (pintype "passive"))
      (node (ref "D22") (pin "1") (pinfunction "A_1") (pintype "passive"))
      (node (ref "D23") (pin "1") (pinfunction "A_1") (pintype "passive"))
      (node (ref "D24") (pin "1") (pinfunction "A_1") (pintype "passive"))
      (node (ref "D25") (pin "1") (pinfunction "A_1") (pintype "passive"))
      (node (ref "D26") (pin "1") (pinfunction "A_1") (pintype "passive"))
      (node (ref "D27") (pin "1") (pinfunction "A_1") (pintype "passive"))
      (node (ref "D6") (pin "1") (pinfunction "A_1") (pintype "passive"))
      (node (ref "D7") (pin "1") (pinfunction "A_1") (pintype "passive"))
      (node (ref "D8") (pin "1") (pinfunction "A_1") (pintype "passive"))
      (node (ref "D9") (pin "1") (pinfunction "A_1") (pintype "passive"))
      (node (ref "U14") (pin "4") (pinfunction "GND_4") (pintype "power_in"))
      (node (ref "U15") (pin "12") (pinfunction "VSS_12") (pintype "passive"))
      (node (ref "U15") (pin "15") (pinfunction "ENABLE_15") (pintype "passive"))
      (node (ref "U16") (pin "13") (pinfunction "~{OE}_13") (pintype "input"))
      (node (ref "U16") (pin "8") (pinfunction "GND_8") (pintype "power_in"))
      (node (ref "U17") (pin "12") (pinfunction "VSS_12") (pintype "passive"))
      (node (ref "U17") (pin "15") (pinfunction "ENABLE_15") (pintype "passive"))
    )
  )
)
